# buslamp-r4_reverse_ESP.net
KiCad netlist of a schematic drawn in EAGLE
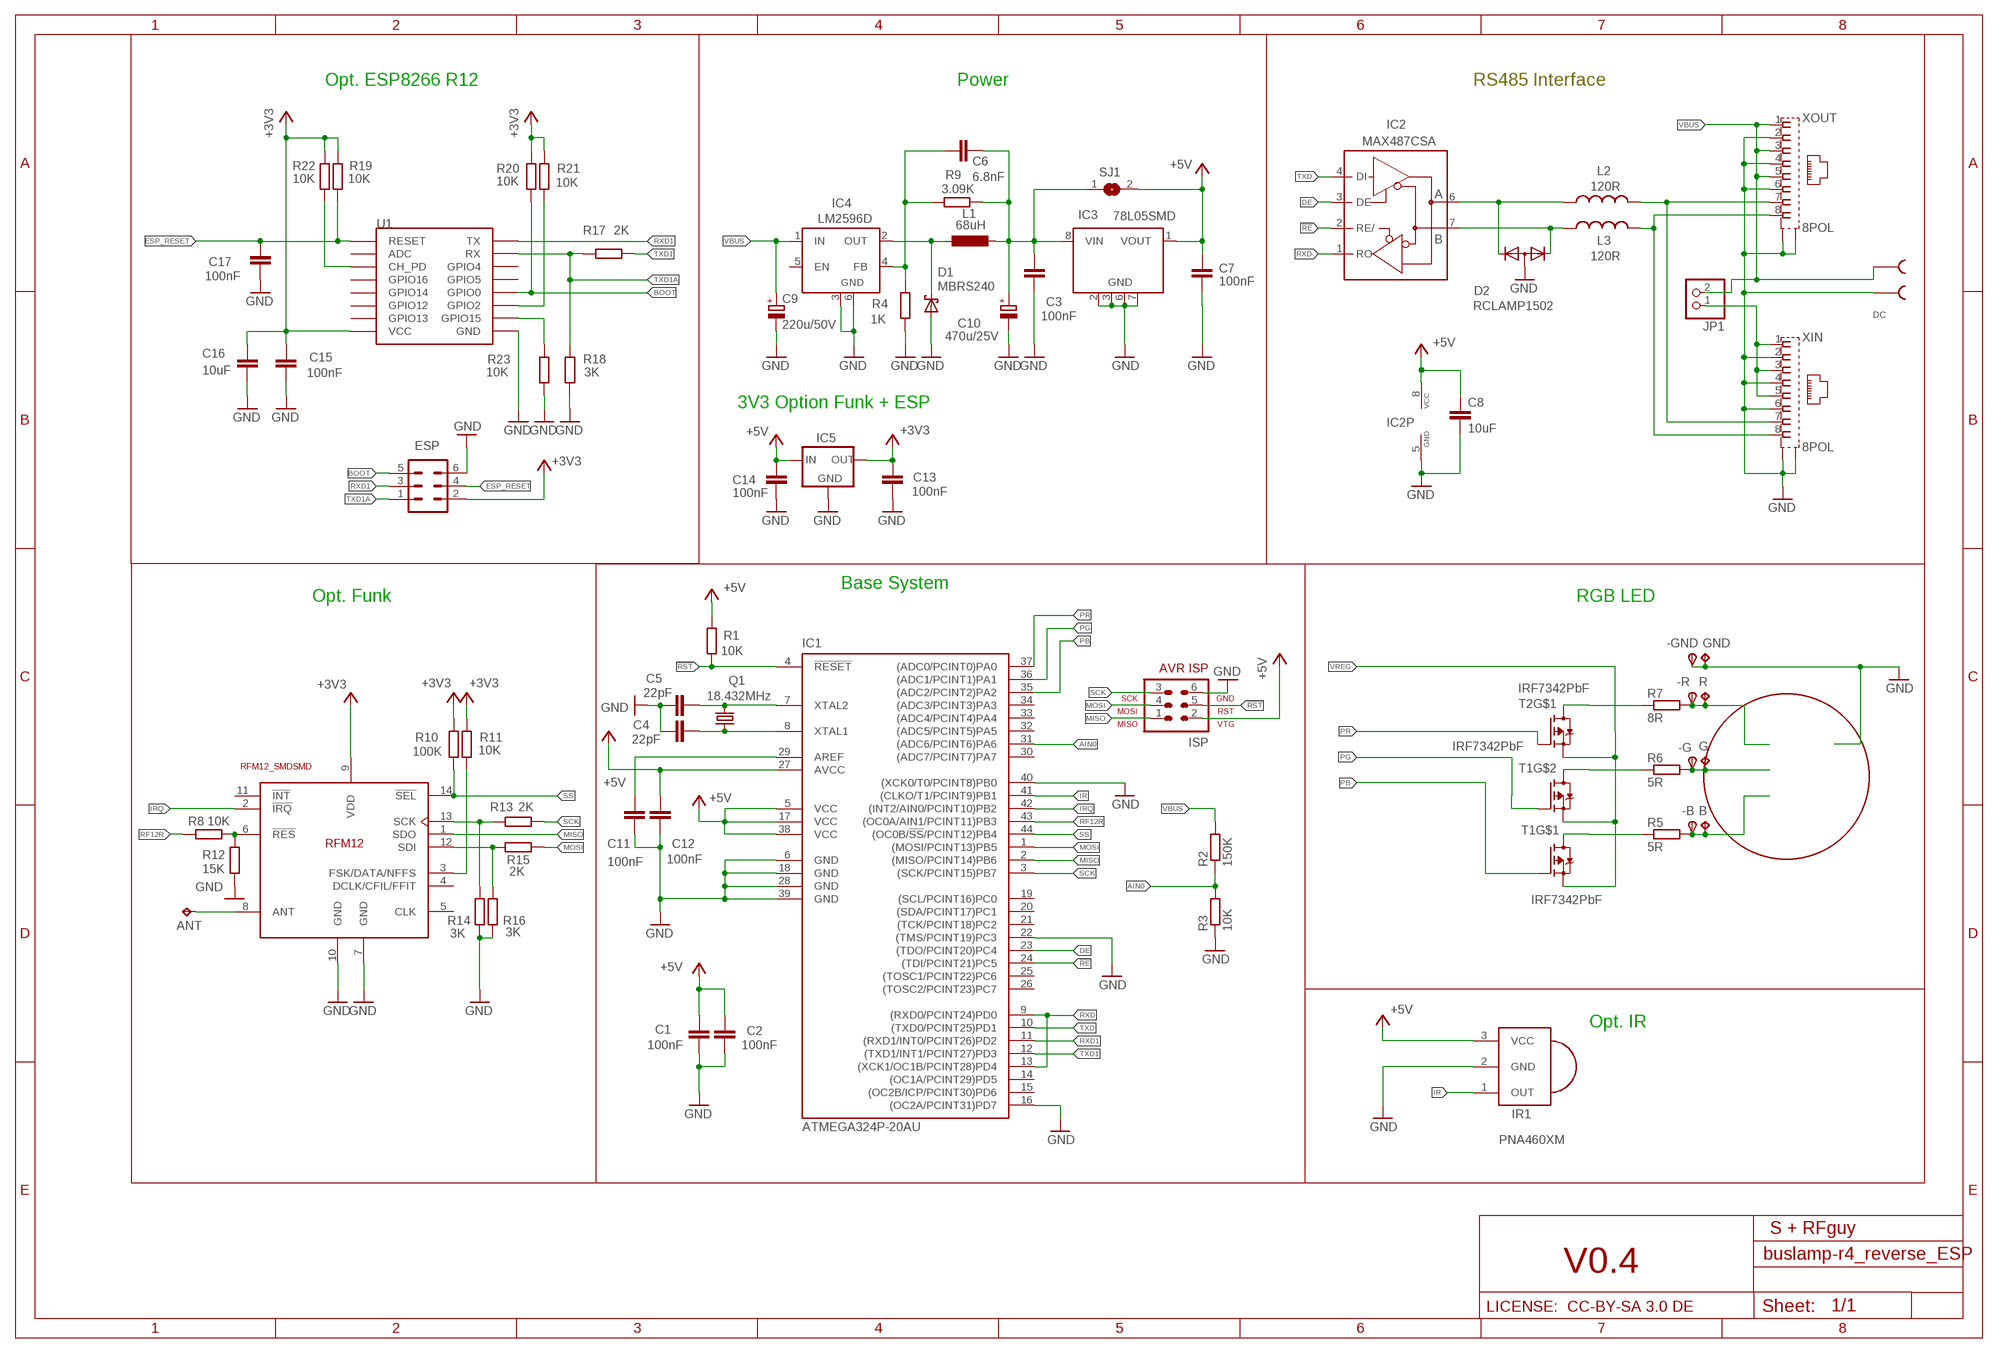
[diagram p0: schematic, sheet 1]

(export (version "E")
  (design (tool "Eeschema 10.0.6"))
  (components
    (comp (ref "-B")
      (value "TPSTP212R")
      (footprint "eagle-import:TP212R")
      (libsource (lib "eagle-import") (part "TPSTP212R"))
    )
    (comp (ref "-G")
      (value "TPSTP212R")
      (footprint "eagle-import:TP212R")
      (libsource (lib "eagle-import") (part "TPSTP212R"))
    )
    (comp (ref "-GND")
      (value "TPSTP212R")
      (footprint "eagle-import:TP212R")
      (libsource (lib "eagle-import") (part "TPSTP212R"))
    )
    (comp (ref "-R")
      (value "TPSTP212R")
      (footprint "eagle-import:TP212R")
      (libsource (lib "eagle-import") (part "TPSTP212R"))
    )
    (comp (ref "ANT")
      (value "TPPAD1-13")
      (footprint "eagle-import:P1-13")
      (libsource (lib "eagle-import") (part "TPPAD1-13"))
    )
    (comp (ref "B")
      (value "TPPAD1-13")
      (footprint "eagle-import:P1-13")
      (libsource (lib "eagle-import") (part "TPPAD1-13"))
    )
    (comp (ref "C1")
      (value "100nF")
      (footprint "eagle-import:C0805K")
      (libsource (lib "eagle-import") (part "C-EUC0805K"))
    )
    (comp (ref "C2")
      (value "100nF")
      (footprint "eagle-import:C0805K")
      (libsource (lib "eagle-import") (part "C-EUC0805K"))
    )
    (comp (ref "C3")
      (value "100nF")
      (footprint "eagle-import:C0805K")
      (libsource (lib "eagle-import") (part "C-EUC0805K"))
    )
    (comp (ref "C4")
      (value "22pF")
      (footprint "eagle-import:C0805K")
      (libsource (lib "eagle-import") (part "C-EUC0805K"))
    )
    (comp (ref "C5")
      (value "22pF")
      (footprint "eagle-import:C0805K")
      (libsource (lib "eagle-import") (part "C-EUC0805K"))
    )
    (comp (ref "C6")
      (value "6.8nF")
      (footprint "eagle-import:C0805K")
      (libsource (lib "eagle-import") (part "C-EUC0805K"))
    )
    (comp (ref "C7")
      (value "100nF")
      (footprint "eagle-import:C0805K")
      (libsource (lib "eagle-import") (part "C-EUC0805K"))
    )
    (comp (ref "C8")
      (value "10uF")
      (footprint "eagle-import:C1210")
      (libsource (lib "eagle-import") (part "C-EUC1210"))
    )
    (comp (ref "C9")
      (value "220u/50V")
      (footprint "eagle-import:UD-10X10_NICHICON")
      (libsource (lib "eagle-import") (part "CPOL-EUUD-10X10"))
    )
    (comp (ref "C10")
      (value "470u/25V")
      (footprint "eagle-import:UD-10X10_NICHICON")
      (libsource (lib "eagle-import") (part "CPOL-EUUD-10X10"))
    )
    (comp (ref "C11")
      (value "100nF")
      (footprint "eagle-import:C0805")
      (libsource (lib "eagle-import") (part "C-EUC0805"))
    )
    (comp (ref "C12")
      (value "100nF")
      (footprint "eagle-import:C0805")
      (libsource (lib "eagle-import") (part "C-EUC0805"))
    )
    (comp (ref "C13")
      (value "100nF")
      (footprint "eagle-import:C0805")
      (libsource (lib "eagle-import") (part "C-EUC0805"))
    )
    (comp (ref "C14")
      (value "100nF")
      (footprint "eagle-import:C0805")
      (libsource (lib "eagle-import") (part "C-EUC0805"))
    )
    (comp (ref "C15")
      (value "100nF")
      (footprint "eagle-import:C0805")
      (libsource (lib "eagle-import") (part "C-EUC0805"))
    )
    (comp (ref "C16")
      (value "10uF")
      (footprint "eagle-import:C1210")
      (libsource (lib "eagle-import") (part "C-EUC1210"))
    )
    (comp (ref "C17")
      (value "100nF")
      (footprint "eagle-import:C0805")
      (libsource (lib "eagle-import") (part "C-EUC0805"))
    )
    (comp (ref "D1")
      (value "MBRS240")
      (footprint "eagle-import:SMB")
      (libsource (lib "eagle-import") (part "MBRS130LT3"))
    )
    (comp (ref "D2")
      (value "RCLAMP1502")
      (footprint "eagle-import:SOT23")
      (libsource (lib "eagle-import") (part "DIODE-2CA|ACSOT23"))
    )
    (comp (ref "DC")
      (value "STL-266-2")
      (footprint "eagle-import:STL-266-2")
      (libsource (lib "eagle-import") (part "STL-266-2"))
    )
    (comp (ref "ESP")
      (value "MA03-2")
      (footprint "eagle-import:MA03-2")
      (libsource (lib "eagle-import") (part "MA03-2"))
    )
    (comp (ref "G")
      (value "TPPAD1-13")
      (footprint "eagle-import:P1-13")
      (libsource (lib "eagle-import") (part "TPPAD1-13"))
    )
    (comp (ref "GND")
      (value "TPPAD1-13")
      (footprint "eagle-import:P1-13")
      (libsource (lib "eagle-import") (part "TPPAD1-13"))
    )
    (comp (ref "IC1")
      (value "ATMEGA324P-20AU")
      (footprint "eagle-import:TQFP44")
      (libsource (lib "eagle-import") (part "MEGA164P/324P/644P-AU"))
    )
    (comp (ref "IC2")
      (value "MAX487CSA")
      (footprint "eagle-import:SO08")
      (libsource (lib "eagle-import") (part "MAX481CSA"))
    )
    (comp (ref "IC3")
      (value "78L05SMD")
      (footprint "eagle-import:SO08")
      (libsource (lib "eagle-import") (part "78LSMD05"))
    )
    (comp (ref "IC4")
      (value "LM2596D")
      (footprint "eagle-import:TO263-5")
      (libsource (lib "eagle-import") (part "LM2596S"))
    )
    (comp (ref "IC5")
      (value "MCP1700SOT23")
      (footprint "eagle-import:SOT23")
      (libsource (lib "eagle-import") (part "MCP1700SOT23"))
    )
    (comp (ref "IR1")
      (value "PNA460XM")
      (footprint "eagle-import:PNA460XM")
      (libsource (lib "eagle-import") (part "PNA460XM"))
    )
    (comp (ref "ISP")
      (value "AVR-ISP-6")
      (footprint "eagle-import:AVR-ISP-6")
      (libsource (lib "eagle-import") (part "AVR-ISP-6"))
    )
    (comp (ref "JP1")
      (value "PINHD-1X2")
      (footprint "eagle-import:1X02")
      (libsource (lib "eagle-import") (part "PINHD-1X2"))
    )
    (comp (ref "L1")
      (value "68uH")
      (footprint "eagle-import:PIS4728")
      (libsource (lib "eagle-import") (part "PSI4728"))
    )
    (comp (ref "L2")
      (value "120R")
      (footprint "eagle-import:L0603")
      (libsource (lib "eagle-import") (part "L-USL0603"))
    )
    (comp (ref "L3")
      (value "120R")
      (footprint "eagle-import:L0603")
      (libsource (lib "eagle-import") (part "L-USL0603"))
    )
    (comp (ref "Q1")
      (value "18.432MHz")
      (footprint "eagle-import:HC49_S")
      (libsource (lib "eagle-import") (part "CRYTALHC49S"))
    )
    (comp (ref "R")
      (value "TPPAD1-13")
      (footprint "eagle-import:P1-13")
      (libsource (lib "eagle-import") (part "TPPAD1-13"))
    )
    (comp (ref "R1")
      (value "10K")
      (footprint "eagle-import:M0805")
      (libsource (lib "eagle-import") (part "R-EU_M0805"))
    )
    (comp (ref "R2")
      (value "150K")
      (footprint "eagle-import:R0805")
      (libsource (lib "eagle-import") (part "R-EU_R0805"))
    )
    (comp (ref "R3")
      (value "10K")
      (footprint "eagle-import:R0805")
      (libsource (lib "eagle-import") (part "R-EU_R0805"))
    )
    (comp (ref "R4")
      (value "1K")
      (footprint "eagle-import:M0805")
      (libsource (lib "eagle-import") (part "R-EU_M0805"))
    )
    (comp (ref "R5")
      (value "5R")
      (footprint "eagle-import:0617_17")
      (libsource (lib "eagle-import") (part "rclml_R-EU_0617/17"))
    )
    (comp (ref "R6")
      (value "5R")
      (footprint "eagle-import:0617_17")
      (libsource (lib "eagle-import") (part "rclml_R-EU_0617/17"))
    )
    (comp (ref "R7")
      (value "8R")
      (footprint "eagle-import:0617_17")
      (libsource (lib "eagle-import") (part "rclml_R-EU_0617/17"))
    )
    (comp (ref "R8")
      (value "10K")
      (footprint "eagle-import:M0805")
      (libsource (lib "eagle-import") (part "R-EU_M0805"))
    )
    (comp (ref "R9")
      (value "3.09K")
      (footprint "eagle-import:M0805")
      (libsource (lib "eagle-import") (part "R-EU_M0805"))
    )
    (comp (ref "R10")
      (value "100K")
      (footprint "eagle-import:M0805")
      (libsource (lib "eagle-import") (part "R-EU_M0805"))
    )
    (comp (ref "R11")
      (value "10K")
      (footprint "eagle-import:M0805")
      (libsource (lib "eagle-import") (part "R-EU_M0805"))
    )
    (comp (ref "R12")
      (value "15K")
      (footprint "eagle-import:M0805")
      (libsource (lib "eagle-import") (part "R-EU_M0805"))
    )
    (comp (ref "R13")
      (value "2K")
      (footprint "eagle-import:M0805")
      (libsource (lib "eagle-import") (part "R-EU_M0805"))
    )
    (comp (ref "R14")
      (value "3K")
      (footprint "eagle-import:M0805")
      (libsource (lib "eagle-import") (part "R-EU_M0805"))
    )
    (comp (ref "R15")
      (value "2K")
      (footprint "eagle-import:M0805")
      (libsource (lib "eagle-import") (part "R-EU_M0805"))
    )
    (comp (ref "R16")
      (value "3K")
      (footprint "eagle-import:M0805")
      (libsource (lib "eagle-import") (part "R-EU_M0805"))
    )
    (comp (ref "R17")
      (value "2K")
      (footprint "eagle-import:M0805")
      (libsource (lib "eagle-import") (part "R-EU_M0805"))
    )
    (comp (ref "R18")
      (value "3K")
      (footprint "eagle-import:M0805")
      (libsource (lib "eagle-import") (part "R-EU_M0805"))
    )
    (comp (ref "R19")
      (value "10K")
      (footprint "eagle-import:M0805")
      (libsource (lib "eagle-import") (part "R-EU_M0805"))
    )
    (comp (ref "R20")
      (value "10K")
      (footprint "eagle-import:M0805")
      (libsource (lib "eagle-import") (part "R-EU_M0805"))
    )
    (comp (ref "R21")
      (value "10K")
      (footprint "eagle-import:M0805")
      (libsource (lib "eagle-import") (part "R-EU_M0805"))
    )
    (comp (ref "R22")
      (value "10K")
      (footprint "eagle-import:M0805")
      (libsource (lib "eagle-import") (part "R-EU_M0805"))
    )
    (comp (ref "R23")
      (value "10K")
      (footprint "eagle-import:M0805")
      (libsource (lib "eagle-import") (part "R-EU_M0805"))
    )
    (comp (ref "RF1")
      (value "RFM12_SMDSMD")
      (footprint "eagle-import:RFM12")
      (libsource (lib "eagle-import") (part "RFM12_SMDSMD"))
    )
    (comp (ref "SJ1") (value "SJ") (footprint "eagle-import:SJ") (libsource (lib "eagle-import") (part "SJ")))
    (comp (ref "T1")
      (value "IRF7342PbF")
      (footprint "eagle-import:SO08-IRF")
      (libsource (lib "eagle-import") (part "IRF7342PBF"))
    )
    (comp (ref "T2")
      (value "IRF7342PbF")
      (footprint "eagle-import:SO08-IRF")
      (libsource (lib "eagle-import") (part "IRF7342PBF"))
    )
    (comp (ref "U$2")
      (value "KK-STERN")
      (footprint "eagle-import:STERN")
      (libsource (lib "eagle-import") (part "KK-STERN"))
    )
    (comp (ref "U1")
      (value "ESP12SMD")
      (footprint "eagle-import:ESP12-SMD")
      (libsource (lib "eagle-import") (part "ESP12SMD"))
    )
    (comp (ref "XIN")
      (value "8POL")
      (footprint "eagle-import:8POL")
      (libsource (lib "eagle-import") (part "8POL"))
    )
    (comp (ref "XOUT")
      (value "8POL")
      (footprint "eagle-import:8POL")
      (libsource (lib "eagle-import") (part "8POL"))
    )
  )
  (nets
    (net (code "1") (name "+3V3") (class "Default")
      (node (ref "C13") (pin "2") (pinfunction "2_2") (pintype "passive"))
      (node (ref "C15") (pin "2") (pinfunction "2_2") (pintype "passive"))
      (node (ref "C16") (pin "1") (pinfunction "1_1") (pintype "passive"))
      (node (ref "ESP") (pin "2") (pinfunction "2_2") (pintype "passive"))
      (node (ref "IC5") (pin "2") (pinfunction "OUT_2") (pintype "passive"))
      (node (ref "R10") (pin "1") (pinfunction "1_1") (pintype "passive"))
      (node (ref "R11") (pin "1") (pinfunction "1_1") (pintype "passive"))
      (node (ref "R19") (pin "1") (pinfunction "1_1") (pintype "passive"))
      (node (ref "R20") (pin "1") (pinfunction "1_1") (pintype "passive"))
      (node (ref "R21") (pin "1") (pinfunction "1_1") (pintype "passive"))
      (node (ref "R22") (pin "1") (pinfunction "1_1") (pintype "passive"))
      (node (ref "RF1") (pin "9") (pinfunction "VDD_9") (pintype "power_in"))
      (node (ref "U1") (pin "VCC") (pinfunction "VCC_VCC") (pintype "bidirectional"))
    )
    (net (code "2") (name "+5V") (class "Default")
      (node (ref "C1") (pin "1") (pinfunction "1_1") (pintype "passive"))
      (node (ref "C12") (pin "2") (pinfunction "2_2") (pintype "passive"))
      (node (ref "C14") (pin "2") (pinfunction "2_2") (pintype "passive"))
      (node (ref "C2") (pin "1") (pinfunction "1_1") (pintype "passive"))
      (node (ref "C7") (pin "1") (pinfunction "1_1") (pintype "passive"))
      (node (ref "C8") (pin "1") (pinfunction "1_1") (pintype "passive"))
      (node (ref "IC1") (pin "17") (pinfunction "VCC_17") (pintype "power_in"))
      (node (ref "IC1") (pin "27") (pinfunction "AVCC_27") (pintype "power_in"))
      (node (ref "IC1") (pin "38") (pinfunction "VCC_38") (pintype "power_in"))
      (node (ref "IC1") (pin "5") (pinfunction "VCC_5") (pintype "power_in"))
      (node (ref "IC2") (pin "8") (pinfunction "VCC_8") (pintype "power_in"))
      (node (ref "IC3") (pin "1") (pinfunction "VOUT_1") (pintype "output"))
      (node (ref "IC5") (pin "3") (pinfunction "IN_3") (pintype "input"))
      (node (ref "IR1") (pin "3") (pinfunction "VCC_3") (pintype "power_in"))
      (node (ref "ISP") (pin "2") (pinfunction "2_2") (pintype "passive"))
      (node (ref "R1") (pin "2") (pinfunction "2_2") (pintype "passive"))
      (node (ref "SJ1") (pin "2") (pinfunction "2_2") (pintype "passive"))
    )
    (net (code "3") (name "/~{RE}") (class "Default")
      (node (ref "IC1") (pin "24") (pinfunction "(TDI/PCINT21)PC5_24") (pintype "bidirectional"))
      (node (ref "IC2") (pin "2") (pinfunction "RE/_2") (pintype "input"))
    )
    (net (code "4") (name "/~{RST}") (class "Default")
      (node (ref "IC1") (pin "4") (pinfunction "~{RESET}_4") (pintype "input"))
      (node (ref "ISP") (pin "5") (pinfunction "5_5") (pintype "passive"))
      (node (ref "R1") (pin "1") (pinfunction "1_1") (pintype "passive"))
    )
    (net (code "5") (name "AIN0") (class "Default")
      (node (ref "IC1") (pin "31") (pinfunction "(ADC6/PCINT6)PA6_31") (pintype "bidirectional"))
      (node (ref "R2") (pin "1") (pinfunction "1_1") (pintype "passive"))
      (node (ref "R3") (pin "2") (pinfunction "2_2") (pintype "passive"))
    )
    (net (code "6") (name "BOOT") (class "Default")
      (node (ref "ESP") (pin "5") (pinfunction "5_5") (pintype "passive"))
      (node (ref "R20") (pin "2") (pinfunction "2_2") (pintype "passive"))
      (node (ref "U1") (pin "GPIO0") (pinfunction "GPIO0_GPIO0") (pintype "bidirectional"))
    )
    (net (code "7") (name "DE") (class "Default")
      (node (ref "IC1") (pin "23") (pinfunction "(TDO/PCINT20)PC4_23") (pintype "bidirectional"))
      (node (ref "IC2") (pin "3") (pinfunction "DE_3") (pintype "input"))
    )
    (net (code "8") (name "ESP_RESET") (class "Default")
      (node (ref "C17") (pin "2") (pinfunction "2_2") (pintype "passive"))
      (node (ref "ESP") (pin "4") (pinfunction "4_4") (pintype "passive"))
      (node (ref "R19") (pin "2") (pinfunction "2_2") (pintype "passive"))
      (node (ref "U1") (pin "RESET") (pinfunction "RESET_RESET") (pintype "bidirectional"))
    )
    (net (code "9") (name "GND") (class "Default")
      (node (ref "-GND") (pin "TP") (pinfunction "PP_TP") (pintype "input"))
      (node (ref "C1") (pin "2") (pinfunction "2_2") (pintype "passive"))
      (node (ref "C10") (pin "-") (pinfunction "-_-") (pintype "passive"))
      (node (ref "C11") (pin "1") (pinfunction "1_1") (pintype "passive"))
      (node (ref "C12") (pin "1") (pinfunction "1_1") (pintype "passive"))
      (node (ref "C13") (pin "1") (pinfunction "1_1") (pintype "passive"))
      (node (ref "C14") (pin "1") (pinfunction "1_1") (pintype "passive"))
      (node (ref "C15") (pin "1") (pinfunction "1_1") (pintype "passive"))
      (node (ref "C16") (pin "2") (pinfunction "2_2") (pintype "passive"))
      (node (ref "C17") (pin "1") (pinfunction "1_1") (pintype "passive"))
      (node (ref "C2") (pin "2") (pinfunction "2_2") (pintype "passive"))
      (node (ref "C3") (pin "2") (pinfunction "2_2") (pintype "passive"))
      (node (ref "C4") (pin "1") (pinfunction "1_1") (pintype "passive"))
      (node (ref "C5") (pin "1") (pinfunction "1_1") (pintype "passive"))
      (node (ref "C7") (pin "2") (pinfunction "2_2") (pintype "passive"))
      (node (ref "C8") (pin "2") (pinfunction "2_2") (pintype "passive"))
      (node (ref "C9") (pin "-") (pinfunction "-_-") (pintype "passive"))
      (node (ref "D1") (pin "A") (pinfunction "A_A") (pintype "passive"))
      (node (ref "D2") (pin "3") (pinfunction "A_3") (pintype "passive"))
      (node (ref "DC") (pin "P$3") (pinfunction "P$1_P$3") (pintype "bidirectional"))
      (node (ref "ESP") (pin "6") (pinfunction "6_6") (pintype "passive"))
      (node (ref "GND") (pin "TP") (pinfunction "TP_TP") (pintype "input"))
      (node (ref "IC1") (pin "16") (pinfunction "(OC2A/PCINT31)PD7_16") (pintype "bidirectional"))
      (node (ref "IC1") (pin "18") (pinfunction "GND_18") (pintype "power_in"))
      (node (ref "IC1") (pin "22") (pinfunction "(TMS/PCINT19)PC3_22") (pintype "bidirectional"))
      (node (ref "IC1") (pin "28") (pinfunction "GND_28") (pintype "power_in"))
      (node (ref "IC1") (pin "39") (pinfunction "GND_39") (pintype "power_in"))
      (node (ref "IC1") (pin "40") (pinfunction "(XCK0/T0/PCINT8)PB0_40") (pintype "bidirectional"))
      (node (ref "IC1") (pin "6") (pinfunction "GND_6") (pintype "power_in"))
      (node (ref "IC2") (pin "5") (pinfunction "GND_5") (pintype "power_in"))
      (node (ref "IC3") (pin "2") (pinfunction "GND_2") (pintype "power_in"))
      (node (ref "IC3") (pin "3") (pinfunction "GND_3") (pintype "power_in"))
      (node (ref "IC3") (pin "6") (pinfunction "GND_6") (pintype "power_in"))
      (node (ref "IC3") (pin "7") (pinfunction "GND_7") (pintype "power_in"))
      (node (ref "IC4") (pin "3") (pinfunction "GND_3") (pintype "power_in"))
      (node (ref "IC4") (pin "6") (pinfunction "GND_6") (pintype "power_in"))
      (node (ref "IC5") (pin "1") (pinfunction "GND_1") (pintype "input"))
      (node (ref "IR1") (pin "2") (pinfunction "GND_2") (pintype "power_in"))
      (node (ref "ISP") (pin "6") (pinfunction "6_6") (pintype "passive"))
      (node (ref "R12") (pin "2") (pinfunction "2_2") (pintype "passive"))
      (node (ref "R14") (pin "2") (pinfunction "2_2") (pintype "passive"))
      (node (ref "R16") (pin "2") (pinfunction "2_2") (pintype "passive"))
      (node (ref "R18") (pin "2") (pinfunction "2_2") (pintype "passive"))
      (node (ref "R23") (pin "2") (pinfunction "2_2") (pintype "passive"))
      (node (ref "R3") (pin "1") (pinfunction "1_1") (pintype "passive"))
      (node (ref "R4") (pin "2") (pinfunction "2_2") (pintype "passive"))
      (node (ref "RF1") (pin "10") (pinfunction "GND_10") (pintype "passive"))
      (node (ref "RF1") (pin "7") (pinfunction "GND_7") (pintype "passive"))
      (node (ref "U1") (pin "GND") (pinfunction "GND_GND") (pintype "bidirectional"))
      (node (ref "XIN") (pin "2") (pinfunction "2_2") (pintype "passive"))
      (node (ref "XIN") (pin "4") (pinfunction "4_4") (pintype "passive"))
      (node (ref "XIN") (pin "6") (pinfunction "6_6") (pintype "passive"))
      (node (ref "XIN") (pin "S1") (pinfunction "S1_S1") (pintype "passive"))
      (node (ref "XIN") (pin "S2") (pinfunction "S2_S2") (pintype "passive"))
      (node (ref "XOUT") (pin "2") (pinfunction "2_2") (pintype "passive"))
      (node (ref "XOUT") (pin "4") (pinfunction "4_4") (pintype "passive"))
      (node (ref "XOUT") (pin "6") (pinfunction "6_6") (pintype "passive"))
      (node (ref "XOUT") (pin "S1") (pinfunction "S1_S1") (pintype "passive"))
      (node (ref "XOUT") (pin "S2") (pinfunction "S2_S2") (pintype "passive"))
    )
    (net (code "10") (name "IR") (class "Default")
      (node (ref "IC1") (pin "41") (pinfunction "(CLKO/T1/PCINT9)PB1_41") (pintype "bidirectional"))
      (node (ref "IR1") (pin "1") (pinfunction "OUT_1") (pintype "output"))
    )
    (net (code "11") (name "IRQ") (class "Default")
      (node (ref "IC1") (pin "42") (pinfunction "(INT2/AIN0/PCINT10)PB2_42") (pintype "bidirectional"))
      (node (ref "RF1") (pin "2") (pinfunction "~{IRQ}_2") (pintype "output"))
    )
    (net (code "12") (name "MISO") (class "Default")
      (node (ref "IC1") (pin "2") (pinfunction "(MISO/PCINT14)PB6_2") (pintype "bidirectional"))
      (node (ref "ISP") (pin "1") (pinfunction "1_1") (pintype "passive"))
      (node (ref "RF1") (pin "1") (pinfunction "SDO_1") (pintype "output"))
    )
    (net (code "13") (name "MOSI") (class "Default")
      (node (ref "IC1") (pin "1") (pinfunction "(MOSI/PCINT13)PB5_1") (pintype "bidirectional"))
      (node (ref "ISP") (pin "4") (pinfunction "4_4") (pintype "passive"))
      (node (ref "R15") (pin "2") (pinfunction "2_2") (pintype "passive"))
    )
    (net (code "14") (name "Net-(-B-PP)") (class "Default")
      (node (ref "-B") (pin "TP") (pinfunction "PP_TP") (pintype "input"))
      (node (ref "B") (pin "TP") (pinfunction "TP_TP") (pintype "input"))
      (node (ref "R5") (pin "2") (pinfunction "2_2") (pintype "passive"))
    )
    (net (code "15") (name "Net-(-G-PP)") (class "Default")
      (node (ref "-G") (pin "TP") (pinfunction "PP_TP") (pintype "input"))
      (node (ref "G") (pin "TP") (pinfunction "TP_TP") (pintype "input"))
      (node (ref "R6") (pin "2") (pinfunction "2_2") (pintype "passive"))
    )
    (net (code "16") (name "Net-(-R-PP)") (class "Default")
      (node (ref "-R") (pin "TP") (pinfunction "PP_TP") (pintype "input"))
      (node (ref "R") (pin "TP") (pinfunction "TP_TP") (pintype "input"))
      (node (ref "R7") (pin "2") (pinfunction "2_2") (pintype "passive"))
    )
    (net (code "17") (name "Net-(D2-K1)") (class "Default")
      (node (ref "D2") (pin "1") (pinfunction "K1_1") (pintype "passive"))
      (node (ref "IC2") (pin "7") (pinfunction "B_7") (pintype "passive"))
      (node (ref "L3") (pin "1") (pinfunction "1_1") (pintype "passive"))
    )
    (net (code "18") (name "Net-(D2-K2)") (class "Default")
      (node (ref "D2") (pin "2") (pinfunction "K2_2") (pintype "passive"))
      (node (ref "IC2") (pin "6") (pinfunction "A_6") (pintype "passive"))
      (node (ref "L2") (pin "1") (pinfunction "1_1") (pintype "passive"))
    )
    (net (code "19") (name "Net-(IC1-AREF)") (class "Default")
      (node (ref "C11") (pin "2") (pinfunction "2_2") (pintype "passive"))
      (node (ref "IC1") (pin "29") (pinfunction "AREF_29") (pintype "power_in"))
    )
    (net (code "20") (name "Net-(IC1-XTAL1)") (class "Default")
      (node (ref "C4") (pin "2") (pinfunction "2_2") (pintype "passive"))
      (node (ref "IC1") (pin "8") (pinfunction "XTAL1_8") (pintype "input"))
      (node (ref "Q1") (pin "1") (pinfunction "1_1") (pintype "passive"))
    )
    (net (code "21") (name "Net-(IC1-XTAL2)") (class "Default")
      (node (ref "C5") (pin "2") (pinfunction "2_2") (pintype "passive"))
      (node (ref "IC1") (pin "7") (pinfunction "XTAL2_7") (pintype "output"))
      (node (ref "Q1") (pin "2") (pinfunction "2_2") (pintype "passive"))
    )
    (net (code "22") (name "Net-(IC4-FB)") (class "Default")
      (node (ref "C6") (pin "1") (pinfunction "1_1") (pintype "passive"))
      (node (ref "IC4") (pin "4") (pinfunction "FB_4") (pintype "input"))
      (node (ref "R4") (pin "1") (pinfunction "1_1") (pintype "passive"))
      (node (ref "R9") (pin "2") (pinfunction "2_2") (pintype "passive"))
    )
    (net (code "23") (name "Net-(IC4-OUT)") (class "Default")
      (node (ref "D1") (pin "C") (pinfunction "C_C") (pintype "passive"))
      (node (ref "IC4") (pin "2") (pinfunction "OUT_2") (pintype "output"))
      (node (ref "L1") (pin "1") (pinfunction "1_1") (pintype "passive"))
    )
    (net (code "24") (name "Net-(JP1-Pad1)") (class "Default")
      (node (ref "JP1") (pin "1") (pinfunction "1_1") (pintype "passive"))
      (node (ref "XIN") (pin "1") (pinfunction "1_1") (pintype "passive"))
      (node (ref "XIN") (pin "3") (pinfunction "3_3") (pintype "passive"))
      (node (ref "XIN") (pin "5") (pinfunction "5_5") (pintype "passive"))
    )
    (net (code "25") (name "Net-(L2-Pad2)") (class "Default")
      (node (ref "L2") (pin "2") (pinfunction "2_2") (pintype "passive"))
      (node (ref "XIN") (pin "7") (pinfunction "7_7") (pintype "passive"))
      (node (ref "XOUT") (pin "7") (pinfunction "7_7") (pintype "passive"))
    )
    (net (code "26") (name "Net-(L3-Pad2)") (class "Default")
      (node (ref "L3") (pin "2") (pinfunction "2_2") (pintype "passive"))
      (node (ref "XIN") (pin "8") (pinfunction "8_8") (pintype "passive"))
      (node (ref "XOUT") (pin "8") (pinfunction "8_8") (pintype "passive"))
    )
    (net (code "27") (name "Net-(R5-Pad1)") (class "Default")
      (node (ref "R5") (pin "1") (pinfunction "1_1") (pintype "passive"))
      (node (ref "T1") (pin "7") (pinfunction "D_7") (pintype "passive"))
      (node (ref "T1") (pin "8") (pinfunction "D_8") (pintype "passive"))
    )
    (net (code "28") (name "Net-(R6-Pad1)") (class "Default")
      (node (ref "R6") (pin "1") (pinfunction "1_1") (pintype "passive"))
      (node (ref "T1") (pin "5") (pinfunction "D_5") (pintype "passive"))
      (node (ref "T1") (pin "6") (pinfunction "D_6") (pintype "passive"))
    )
    (net (code "29") (name "Net-(R7-Pad1)") (class "Default")
      (node (ref "R7") (pin "1") (pinfunction "1_1") (pintype "passive"))
      (node (ref "T2") (pin "7") (pinfunction "D_7") (pintype "passive"))
      (node (ref "T2") (pin "8") (pinfunction "D_8") (pintype "passive"))
    )
    (net (code "30") (name "Net-(R21-Pad2)") (class "Default")
      (node (ref "R21") (pin "2") (pinfunction "2_2") (pintype "passive"))
      (node (ref "U1") (pin "GPIO2") (pinfunction "GPIO2_GPIO2") (pintype "bidirectional"))
    )
    (net (code "31") (name "Net-(R22-Pad2)") (class "Default")
      (node (ref "R22") (pin "2") (pinfunction "2_2") (pintype "passive"))
      (node (ref "U1") (pin "CH_PD") (pinfunction "CH_PD_CH_PD") (pintype "bidirectional"))
    )
    (net (code "32") (name "Net-(R23-Pad1)") (class "Default")
      (node (ref "R23") (pin "1") (pinfunction "1_1") (pintype "passive"))
      (node (ref "U1") (pin "GPIO15") (pinfunction "GPIO15_GPIO15") (pintype "bidirectional"))
    )
    (net (code "33") (name "Net-(RF1-ANT)") (class "Default")
      (node (ref "ANT") (pin "TP") (pinfunction "TP_TP") (pintype "input"))
      (node (ref "RF1") (pin "8") (pinfunction "ANT_8") (pintype "bidirectional"))
    )
    (net (code "34") (name "Net-(RF1-FSK{slash}DATA{slash}NFFS)") (class "Default")
      (node (ref "R11") (pin "2") (pinfunction "2_2") (pintype "passive"))
      (node (ref "RF1") (pin "3") (pinfunction "FSK/DATA/NFFS_3") (pintype "bidirectional"))
    )
    (net (code "35") (name "Net-(RF1-SCK)") (class "Default")
      (node (ref "R13") (pin "1") (pinfunction "1_1") (pintype "passive"))
      (node (ref "R14") (pin "1") (pinfunction "1_1") (pintype "passive"))
      (node (ref "RF1") (pin "13") (pinfunction "SCK_13") (pintype "input"))
    )
    (net (code "36") (name "Net-(RF1-SDI)") (class "Default")
      (node (ref "R15") (pin "1") (pinfunction "1_1") (pintype "passive"))
      (node (ref "R16") (pin "1") (pinfunction "1_1") (pintype "passive"))
      (node (ref "RF1") (pin "12") (pinfunction "SDI_12") (pintype "input"))
    )
    (net (code "37") (name "Net-(RF1-~{RES})") (class "Default")
      (node (ref "R12") (pin "1") (pinfunction "1_1") (pintype "passive"))
      (node (ref "R8") (pin "2") (pinfunction "2_2") (pintype "passive"))
      (node (ref "RF1") (pin "6") (pinfunction "~{RES}_6") (pintype "bidirectional"))
    )
    (net (code "38") (name "PB") (class "Default")
      (node (ref "IC1") (pin "35") (pinfunction "(ADC2/PCINT2)PA2_35") (pintype "bidirectional"))
      (node (ref "T1") (pin "2") (pinfunction "G_2") (pintype "passive"))
    )
    (net (code "39") (name "PG") (class "Default")
      (node (ref "IC1") (pin "36") (pinfunction "(ADC1/PCINT1)PA1_36") (pintype "bidirectional"))
      (node (ref "T1") (pin "4") (pinfunction "G_4") (pintype "passive"))
    )
    (net (code "40") (name "PR") (class "Default")
      (node (ref "IC1") (pin "37") (pinfunction "(ADC0/PCINT0)PA0_37") (pintype "bidirectional"))
      (node (ref "T2") (pin "2") (pinfunction "G_2") (pintype "passive"))
    )
    (net (code "41") (name "RF12R") (class "Default")
      (node (ref "IC1") (pin "43") (pinfunction "(OC0A/AIN1/PCINT11)PB3_43") (pintype "bidirectional"))
      (node (ref "R8") (pin "1") (pinfunction "1_1") (pintype "passive"))
    )
    (net (code "42") (name "RXD") (class "Default")
      (node (ref "IC1") (pin "13") (pinfunction "(XCK1/OC1B/PCINT28)PD4_13") (pintype "bidirectional"))
      (node (ref "IC1") (pin "9") (pinfunction "(RXD0/PCINT24)PD0_9") (pintype "bidirectional"))
      (node (ref "IC2") (pin "1") (pinfunction "RO_1") (pintype "output"))
    )
    (net (code "43") (name "RXD1") (class "Default")
      (node (ref "ESP") (pin "3") (pinfunction "3_3") (pintype "passive"))
      (node (ref "IC1") (pin "11") (pinfunction "(RXD1/INT0/PCINT26)PD2_11") (pintype "bidirectional"))
      (node (ref "U1") (pin "TXD0") (pinfunction "TX_TXD0") (pintype "bidirectional"))
    )
    (net (code "44") (name "SCK") (class "Default")
      (node (ref "IC1") (pin "3") (pinfunction "(SCK/PCINT15)PB7_3") (pintype "bidirectional"))
      (node (ref "ISP") (pin "3") (pinfunction "3_3") (pintype "passive"))
      (node (ref "R13") (pin "2") (pinfunction "2_2") (pintype "passive"))
    )
    (net (code "45") (name "SS") (class "Default")
      (node (ref "IC1") (pin "44") (pinfunction "(OC0B/~{SS}/PCINT12)PB4_44") (pintype "bidirectional"))
      (node (ref "R10") (pin "2") (pinfunction "2_2") (pintype "passive"))
      (node (ref "RF1") (pin "14") (pinfunction "~{SEL}_14") (pintype "input"))
    )
    (net (code "46") (name "TXD") (class "Default")
      (node (ref "IC1") (pin "10") (pinfunction "(TXD0/PCINT25)PD1_10") (pintype "bidirectional"))
      (node (ref "IC2") (pin "4") (pinfunction "DI_4") (pintype "input"))
    )
    (net (code "47") (name "TXD1") (class "Default")
      (node (ref "IC1") (pin "12") (pinfunction "(TXD1/INT1/PCINT27)PD3_12") (pintype "bidirectional"))
      (node (ref "R17") (pin "2") (pinfunction "2_2") (pintype "passive"))
    )
    (net (code "48") (name "TXD1A") (class "Default")
      (node (ref "ESP") (pin "1") (pinfunction "1_1") (pintype "passive"))
      (node (ref "R17") (pin "1") (pinfunction "1_1") (pintype "passive"))
      (node (ref "R18") (pin "1") (pinfunction "1_1") (pintype "passive"))
      (node (ref "U1") (pin "RXD0") (pinfunction "RX_RXD0") (pintype "bidirectional"))
    )
    (net (code "49") (name "VBUS") (class "Default")
      (node (ref "C9") (pin "+") (pinfunction "+_+") (pintype "passive"))
      (node (ref "DC") (pin "P$4") (pinfunction "P$2_P$4") (pintype "bidirectional"))
      (node (ref "IC4") (pin "1") (pinfunction "IN_1") (pintype "input"))
      (node (ref "JP1") (pin "2") (pinfunction "2_2") (pintype "passive"))
      (node (ref "R2") (pin "2") (pinfunction "2_2") (pintype "passive"))
      (node (ref "XOUT") (pin "1") (pinfunction "1_1") (pintype "passive"))
      (node (ref "XOUT") (pin "3") (pinfunction "3_3") (pintype "passive"))
      (node (ref "XOUT") (pin "5") (pinfunction "5_5") (pintype "passive"))
    )
    (net (code "50") (name "VREG") (class "Default")
      (node (ref "C10") (pin "+") (pinfunction "+_+") (pintype "passive"))
      (node (ref "C3") (pin "1") (pinfunction "1_1") (pintype "passive"))
      (node (ref "C6") (pin "2") (pinfunction "2_2") (pintype "passive"))
      (node (ref "IC3") (pin "8") (pinfunction "VIN_8") (pintype "passive"))
      (node (ref "L1") (pin "2") (pinfunction "2_2") (pintype "passive"))
      (node (ref "R9") (pin "1") (pinfunction "1_1") (pintype "passive"))
      (node (ref "SJ1") (pin "1") (pinfunction "1_1") (pintype "passive"))
      (node (ref "T1") (pin "1") (pinfunction "S_1") (pintype "passive"))
      (node (ref "T1") (pin "3") (pinfunction "S_3") (pintype "passive"))
      (node (ref "T2") (pin "1") (pinfunction "S_1") (pintype "passive"))
    )
    (net (code "51") (name "unconnected-(IC1-(ADC3{slash}PCINT3)PA3-Pad34)") (class "Default")
      (node (ref "IC1") (pin "34") (pinfunction "(ADC3/PCINT3)PA3_34") (pintype "bidirectional"))
    )
    (net (code "52") (name "unconnected-(IC1-(ADC4{slash}PCINT4)PA4-Pad33)") (class "Default")
      (node (ref "IC1") (pin "33") (pinfunction "(ADC4/PCINT4)PA4_33") (pintype "bidirectional"))
    )
    (net (code "53") (name "unconnected-(IC1-(ADC5{slash}PCINT5)PA5-Pad32)") (class "Default")
      (node (ref "IC1") (pin "32") (pinfunction "(ADC5/PCINT5)PA5_32") (pintype "bidirectional"))
    )
    (net (code "54") (name "unconnected-(IC1-(ADC7{slash}PCINT7)PA7-Pad30)") (class "Default")
      (node (ref "IC1") (pin "30") (pinfunction "(ADC7/PCINT7)PA7_30") (pintype "bidirectional"))
    )
    (net (code "55") (name "unconnected-(IC1-(OC1A{slash}PCINT29)PD5-Pad14)") (class "Default")
      (node (ref "IC1") (pin "14") (pinfunction "(OC1A/PCINT29)PD5_14") (pintype "bidirectional"))
    )
    (net (code "56") (name "unconnected-(IC1-(OC2B{slash}ICP{slash}PCINT30)PD6-Pad15)") (class "Default")
      (node (ref "IC1") (pin "15") (pinfunction "(OC2B/ICP/PCINT30)PD6_15") (pintype "bidirectional"))
    )
    (net (code "57") (name "unconnected-(IC1-(SCL{slash}PCINT16)PC0-Pad19)") (class "Default")
      (node (ref "IC1") (pin "19") (pinfunction "(SCL/PCINT16)PC0_19") (pintype "bidirectional"))
    )
    (net (code "58") (name "unconnected-(IC1-(SDA{slash}PCINT17)PC1-Pad20)") (class "Default")
      (node (ref "IC1") (pin "20") (pinfunction "(SDA/PCINT17)PC1_20") (pintype "bidirectional"))
    )
    (net (code "59") (name "unconnected-(IC1-(TCK{slash}PCINT18)PC2-Pad21)") (class "Default")
      (node (ref "IC1") (pin "21") (pinfunction "(TCK/PCINT18)PC2_21") (pintype "bidirectional"))
    )
    (net (code "60") (name "unconnected-(IC1-(TOSC1{slash}PCINT22)PC6-Pad25)") (class "Default")
      (node (ref "IC1") (pin "25") (pinfunction "(TOSC1/PCINT22)PC6_25") (pintype "bidirectional"))
    )
    (net (code "61") (name "unconnected-(IC1-(TOSC2{slash}PCINT23)PC7-Pad26)") (class "Default")
      (node (ref "IC1") (pin "26") (pinfunction "(TOSC2/PCINT23)PC7_26") (pintype "bidirectional"))
    )
    (net (code "62") (name "unconnected-(IC4-EN-Pad5)") (class "Default")
      (node (ref "IC4") (pin "5") (pinfunction "EN_5") (pintype "input"))
    )
    (net (code "63") (name "unconnected-(RF1-CLK-Pad5)") (class "Default")
      (node (ref "RF1") (pin "5") (pinfunction "CLK_5") (pintype "output"))
    )
    (net (code "64") (name "unconnected-(RF1-DCLK{slash}CFIL{slash}FFIT-Pad4)") (class "Default")
      (node (ref "RF1") (pin "4") (pinfunction "DCLK/CFIL/FFIT_4") (pintype "bidirectional"))
    )
    (net (code "65") (name "unconnected-(RF1-~{INT}-Pad11)") (class "Default")
      (node (ref "RF1") (pin "11") (pinfunction "~{INT}_11") (pintype "bidirectional"))
    )
    (net (code "66") (name "unconnected-(U1-PadADC)") (class "Default")
      (node (ref "U1") (pin "ADC") (pinfunction "ADC_ADC") (pintype "bidirectional"))
    )
    (net (code "67") (name "unconnected-(U1-PadGPIO4)") (class "Default")
      (node (ref "U1") (pin "GPIO4") (pinfunction "GPIO4_GPIO4") (pintype "bidirectional"))
    )
    (net (code "68") (name "unconnected-(U1-PadGPIO5)") (class "Default")
      (node (ref "U1") (pin "GPIO5") (pinfunction "GPIO5_GPIO5") (pintype "bidirectional"))
    )
    (net (code "69") (name "unconnected-(U1-PadGPIO12)") (class "Default")
      (node (ref "U1") (pin "GPIO12") (pinfunction "GPIO12_GPIO12") (pintype "bidirectional"))
    )
    (net (code "70") (name "unconnected-(U1-PadGPIO13)") (class "Default")
      (node (ref "U1") (pin "GPIO13") (pinfunction "GPIO13_GPIO13") (pintype "bidirectional"))
    )
    (net (code "71") (name "unconnected-(U1-PadGPIO14)") (class "Default")
      (node (ref "U1") (pin "GPIO14") (pinfunction "GPIO14_GPIO14") (pintype "bidirectional"))
    )
    (net (code "72") (name "unconnected-(U1-PadGPIO16)") (class "Default")
      (node (ref "U1") (pin "GPIO16") (pinfunction "GPIO16_GPIO16") (pintype "bidirectional"))
    )
  )
)
